# Sheet_1_copy.net
KiCad netlist of a schematic drawn in Altium Designer
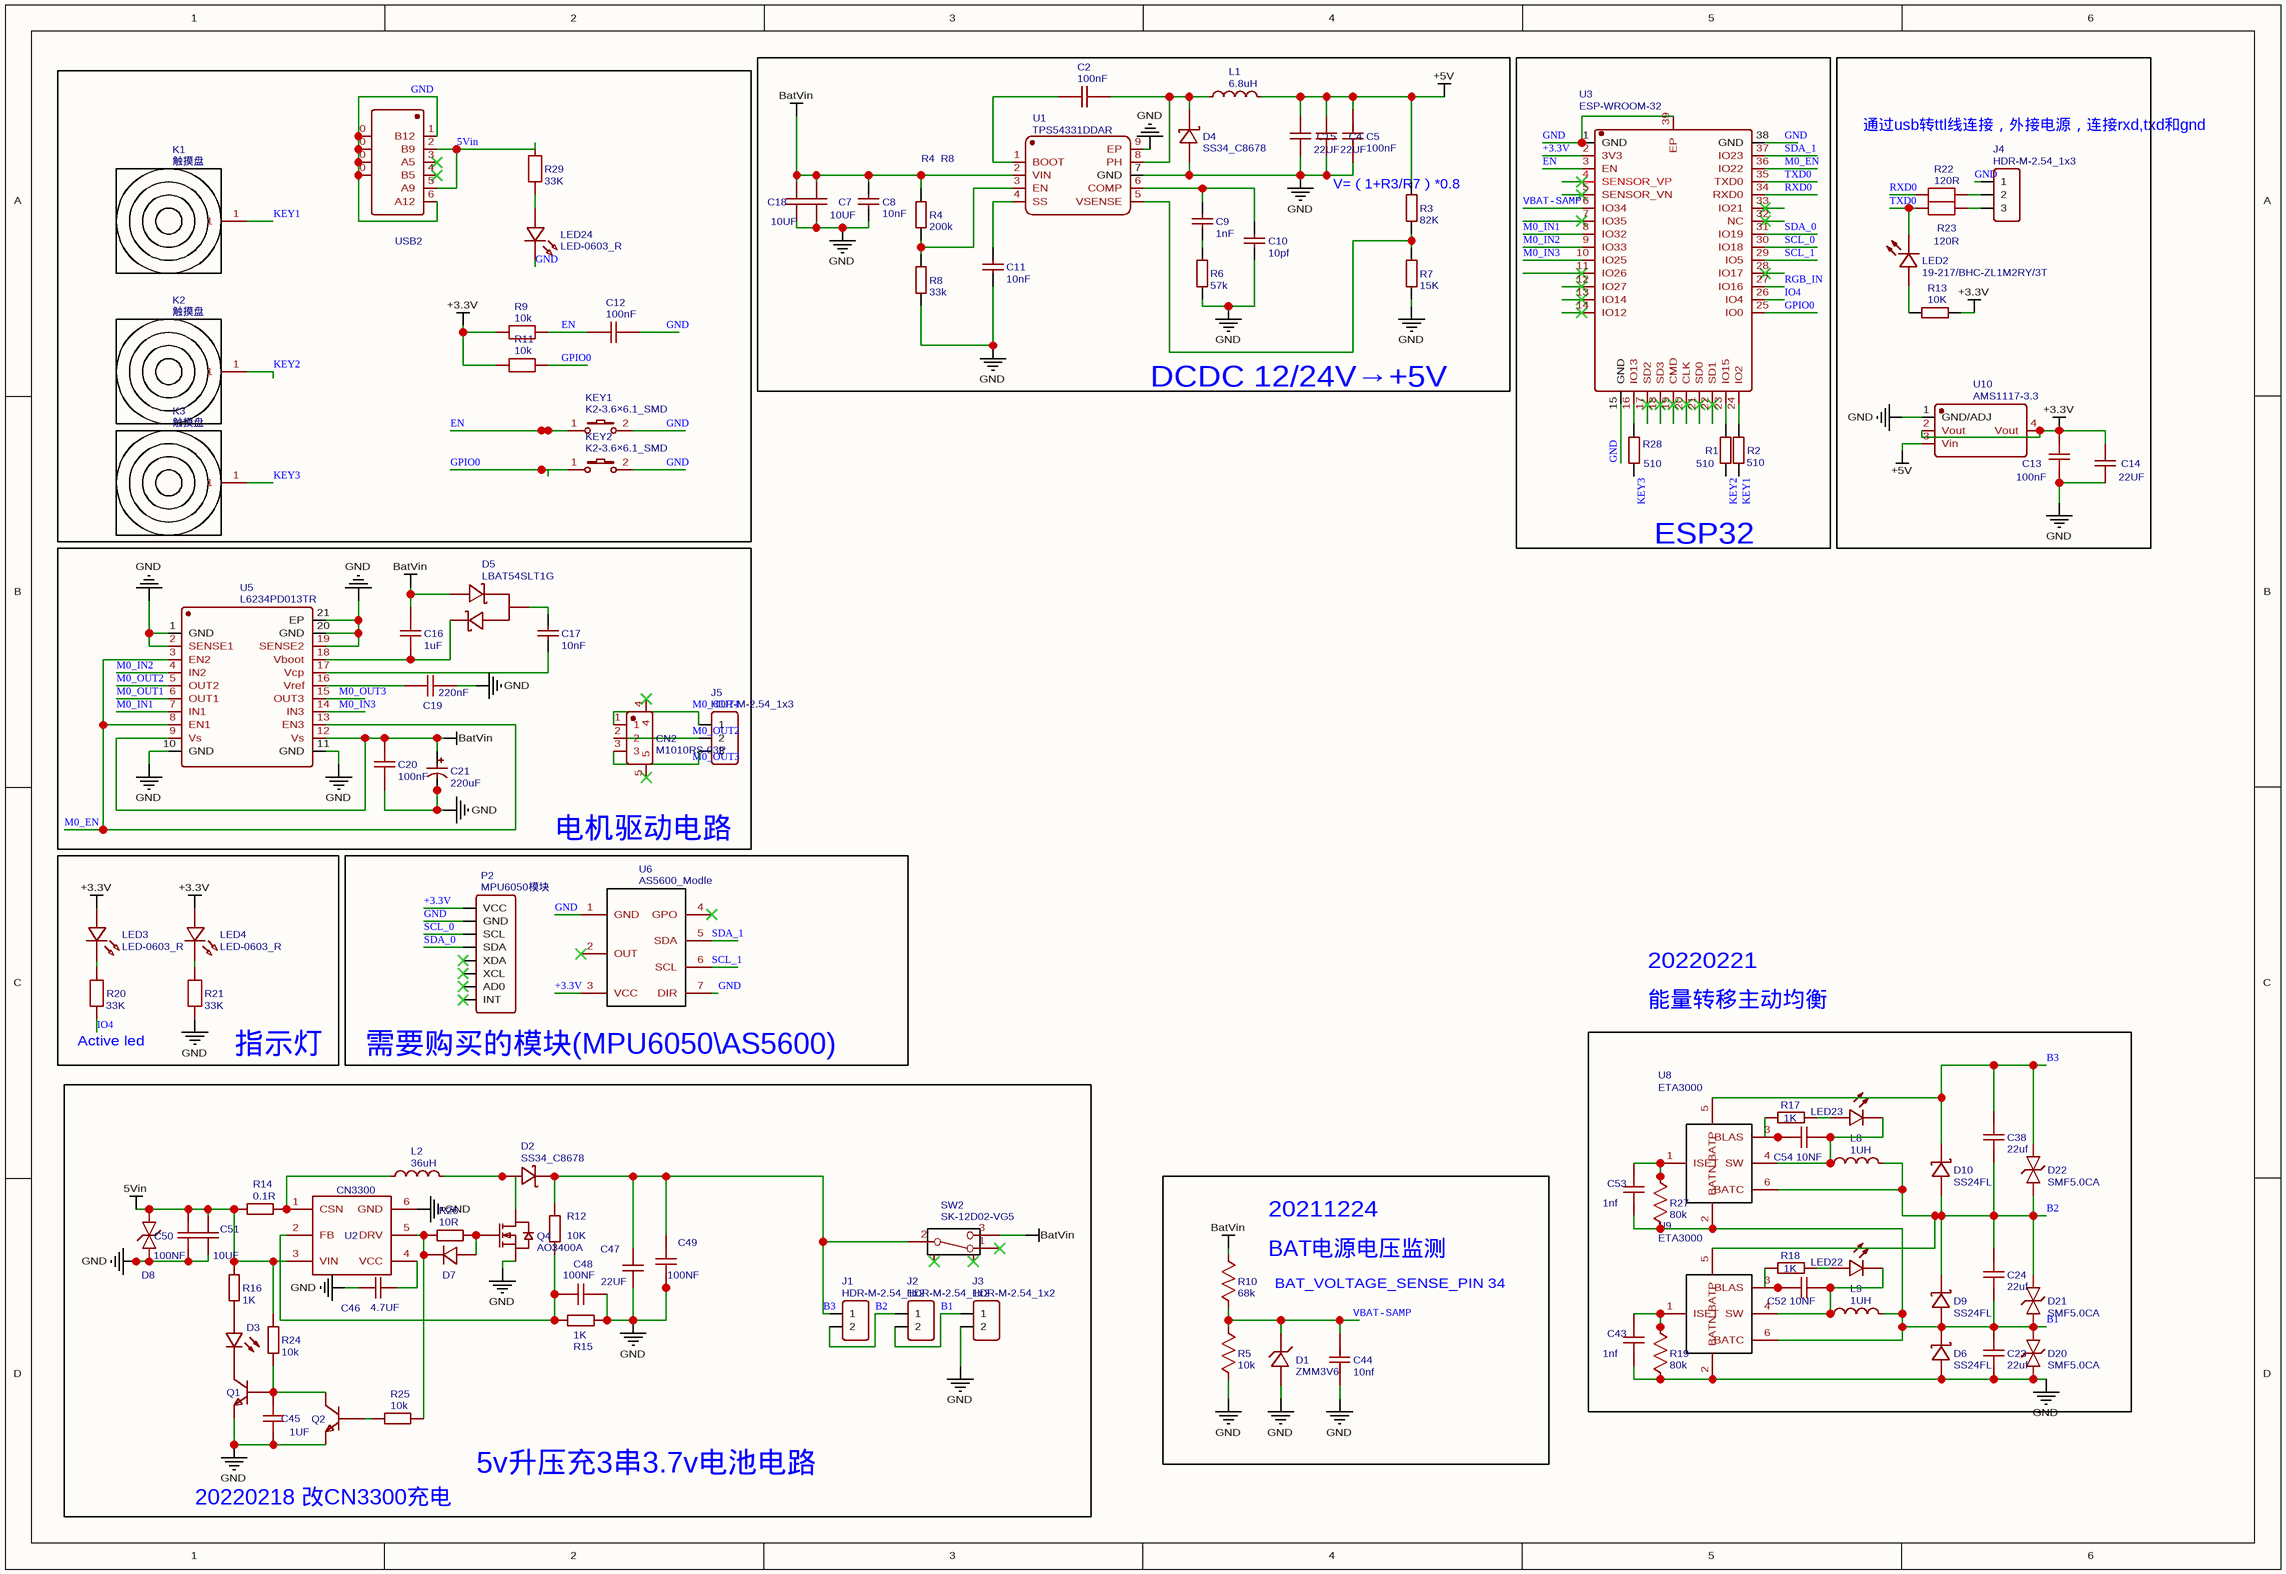
[diagram p0: Sheet_1 copy.schdoc]

(export (version "E")
  (design (tool "Eeschema 10.0.6"))
  (components
    (comp (ref "C2")
      (value "100nF")
      (fields (field (name "BOM_SUPPLIER PART") "C14663") (field (name "CONTRIBUTOR") "LCEDA_Lib"))
      (libsource (lib "altium-import") (part "root_0_100nF_"))
    )
    (comp (ref "C4")
      (value "22UF")
      (fields
        (field (name "BOM_MANUFACTURER PART") "CL31A226KPHNNNE")
        (field (name "BOM_SUPPLIER PART") "C5672")
      )
      (libsource (lib "altium-import") (part "root_1_22UF_"))
    )
    (comp (ref "C5")
      (value "100nF")
      (fields (field (name "BOM_SUPPLIER PART") "C14663") (field (name "CONTRIBUTOR") "LCEDA_Lib"))
      (libsource (lib "altium-import") (part "root_1_100nF_"))
    )
    (comp (ref "C7")
      (value "10UF")
      (fields
        (field (name "BOM_MANUFACTURER PART") "CL31A226KPHNNNE")
        (field (name "BOM_SUPPLIER PART") "C5672")
      )
      (libsource (lib "altium-import") (part "root_1_10UF_"))
    )
    (comp (ref "C8")
      (value "10nF")
      (fields
        (field (name "BOM_MANUFACTURER PART") "CC0603KRX7R9BB103")
        (field (name "BOM_SUPPLIER PART") "C100042")
      )
      (libsource (lib "altium-import") (part "root_1_10nF_"))
    )
    (comp (ref "C9")
      (value "1nF")
      (fields
        (field (name "BOM_MANUFACTURER PART") "CC0603KRX7R9BB102")
        (field (name "BOM_SUPPLIER PART") "C100040")
      )
      (libsource (lib "altium-import") (part "root_1_1nF_"))
    )
    (comp (ref "C10")
      (value "10pf")
      (fields
        (field (name "BOM_MANUFACTURER PART") "CC0603JRNPO9BN470")
        (field (name "BOM_SUPPLIER PART") "C105622")
      )
      (libsource (lib "altium-import") (part "root_1_10pf_"))
    )
    (comp (ref "C11")
      (value "10nF")
      (fields
        (field (name "BOM_MANUFACTURER PART") "CC0603KRX7R9BB103")
        (field (name "BOM_SUPPLIER PART") "C100042")
      )
      (libsource (lib "altium-import") (part "root_1_10nF_"))
    )
    (comp (ref "C12")
      (value "100nF")
      (fields (field (name "BOM_SUPPLIER PART") "C14663") (field (name "CONTRIBUTOR") "LCEDA_Lib"))
      (libsource (lib "altium-import") (part "root_0_100nF_"))
    )
    (comp (ref "C13")
      (value "100nF")
      (fields (field (name "BOM_SUPPLIER PART") "C14663") (field (name "CONTRIBUTOR") "LCEDA_Lib"))
      (libsource (lib "altium-import") (part "root_1_100nF_"))
    )
    (comp (ref "C14")
      (value "22UF")
      (fields
        (field (name "BOM_MANUFACTURER PART") "CL31A226KPHNNNE")
        (field (name "BOM_SUPPLIER PART") "C5672")
      )
      (libsource (lib "altium-import") (part "root_1_22UF_"))
    )
    (comp (ref "C15")
      (value "22UF")
      (fields
        (field (name "BOM_MANUFACTURER PART") "CL31A226KPHNNNE")
        (field (name "BOM_SUPPLIER PART") "C5672")
      )
      (libsource (lib "altium-import") (part "root_1_22UF_"))
    )
    (comp (ref "C16")
      (value "1uF")
      (fields (field (name "CONTRIBUTOR") "LCEDA_Lib"))
      (libsource (lib "altium-import") (part "root_1_1uF_"))
    )
    (comp (ref "C17")
      (value "10nF")
      (fields
        (field (name "BOM_MANUFACTURER PART") "CC0603KRX7R9BB103")
        (field (name "BOM_SUPPLIER PART") "C100042")
      )
      (libsource (lib "altium-import") (part "root_1_10nF_"))
    )
    (comp (ref "C18")
      (value "10UF")
      (fields
        (field (name "BOM_MANUFACTURER PART") "CL31A226KPHNNNE")
        (field (name "BOM_SUPPLIER PART") "C5672")
      )
      (libsource (lib "altium-import") (part "root_1_10UF_"))
    )
    (comp (ref "C19")
      (value "220nF")
      (fields (field (name "CONTRIBUTOR") "LCEDA_Lib"))
      (libsource (lib "altium-import") (part "root_0_220nF_"))
    )
    (comp (ref "C20")
      (value "100nF")
      (fields (field (name "CONTRIBUTOR") "LCEDA_Lib"))
      (libsource (lib "altium-import") (part "root_3_100nF_"))
    )
    (comp (ref "C21")
      (value "220uF")
      (fields (field (name "BOM_MANUFACTURER PART") "220uf/35V") (field (name "BOM_SUPPLIER PART") "C2063"))
      (libsource (lib "altium-import") (part "root_3_220uF_"))
    )
    (comp (ref "C23")
      (value "22uf")
      (fields (field (name "CONTRIBUTOR") "LCEDA_Lib"))
      (libsource (lib "altium-import") (part "root_1_22uf_"))
    )
    (comp (ref "C24")
      (value "22uf")
      (fields (field (name "CONTRIBUTOR") "LCEDA_Lib"))
      (libsource (lib "altium-import") (part "root_1_22uf_"))
    )
    (comp (ref "C38")
      (value "22uf")
      (fields (field (name "CONTRIBUTOR") "LCEDA_Lib"))
      (libsource (lib "altium-import") (part "root_1_22uf_"))
    )
    (comp (ref "C43")
      (value "1nf")
      (fields (field (name "CONTRIBUTOR") "LCEDA_Lib"))
      (libsource (lib "altium-import") (part "root_3_1nf_"))
    )
    (comp (ref "C44")
      (value "10nf")
      (fields (field (name "CONTRIBUTOR") "LCEDA_Lib"))
      (libsource (lib "altium-import") (part "root_1_10nf_"))
    )
    (comp (ref "C45") (value "1UF") (libsource (lib "altium-import") (part "root_0_1UF_")))
    (comp (ref "C46")
      (value "4.7UF")
      (fields
        (field (name "BOM_MANUFACTURER PART") "CL31A226KPHNNNE")
        (field (name "BOM_SUPPLIER PART") "C5672")
      )
      (libsource (lib "altium-import") (part "root_0_4.7UF_"))
    )
    (comp (ref "C47")
      (value "22UF")
      (fields
        (field (name "BOM_MANUFACTURER PART") "CL31A226KPHNNNE")
        (field (name "BOM_SUPPLIER PART") "C5672")
      )
      (libsource (lib "altium-import") (part "root_1_22UF_"))
    )
    (comp (ref "C48") (value "100NF") (libsource (lib "altium-import") (part "root_1_100NF_")))
    (comp (ref "C49") (value "100NF") (libsource (lib "") (part "root_0_100NF__1")))
    (comp (ref "C50") (value "100NF") (libsource (lib "altium-import") (part "root_0_100NF_")))
    (comp (ref "C51")
      (value "10UF")
      (fields
        (field (name "BOM_MANUFACTURER PART") "CL31A226KPHNNNE")
        (field (name "BOM_SUPPLIER PART") "C5672")
      )
      (libsource (lib "altium-import") (part "root_3_10UF_"))
    )
    (comp (ref "C52")
      (value "10NF")
      (fields (field (name "CONTRIBUTOR") "LCEDA_Lib"))
      (libsource (lib "altium-import") (part "root_0_10NF_"))
    )
    (comp (ref "C53")
      (value "1nf")
      (fields (field (name "CONTRIBUTOR") "LCEDA_Lib"))
      (libsource (lib "altium-import") (part "root_3_1nf_"))
    )
    (comp (ref "C54")
      (value "10NF")
      (fields (field (name "CONTRIBUTOR") "LCEDA_Lib"))
      (libsource (lib "altium-import") (part "root_0_10NF_"))
    )
    (comp (ref "CN2")
      (value "M1010RS-03P")
      (fields (field (name "BOM_SUPPLIER PART") "C541845") (field (name "CONTRIBUTOR") "LCSC"))
      (libsource (lib "altium-import") (part "root_0_M1010RS-03P_"))
    )
    (comp (ref "D1")
      (value "ZMM3V6")
      (fields (field (name "BOM_SUPPLIER PART") "C8057"))
      (libsource (lib "altium-import") (part "root_3_ZMM3V6_"))
    )
    (comp (ref "D2")
      (value "SS34_C8678")
      (fields (field (name "BOM_MANUFACTURER PART") "SS34") (field (name "BOM_SUPPLIER PART") "C8678"))
      (libsource (lib "altium-import") (part "root_2_SS34_C8678_"))
    )
    (comp (ref "D3")
      (value "FC-DA1608HRK-620D")
      (fields (field (name "BOM_SUPPLIER PART") "C84263"))
      (libsource (lib "altium-import") (part "root_3_FC-DA1608HRK-620D_"))
    )
    (comp (ref "D4")
      (value "SS34_C8678")
      (fields (field (name "BOM_MANUFACTURER PART") "SS34") (field (name "BOM_SUPPLIER PART") "C8678"))
      (libsource (lib "altium-import") (part "root_3_SS34_C8678_"))
    )
    (comp (ref "D5")
      (value "LBAT54SLT1G")
      (fields (field (name "BOM_SUPPLIER PART") "C12765"))
      (libsource (lib "altium-import") (part "root_0_LBAT54SLT1G_"))
    )
    (comp (ref "D6")
      (value "SS24FL")
      (fields (field (name "BOM_SUPPLIER PART") "C489144") (field (name "CONTRIBUTOR") "LCSC"))
      (libsource (lib "altium-import") (part "root_3_SS24FL_"))
    )
    (comp (ref "D7")
      (value "1N4148WS-C108805")
      (fields (field (name "BOM_MANUFACTURER PART") "1N4148WS") (field (name "BOM_SUPPLIER PART") "C108805"))
      (libsource (lib "altium-import") (part "root_0_1N4148WS-C108805_"))
    )
    (comp (ref "D8")
      (value "SJD12C6.5L01")
      (fields (field (name "BOM_SUPPLIER PART") "C313294") (field (name "CONTRIBUTOR") "LCSC"))
      (libsource (lib "altium-import") (part "root_1_SJD12C6.5L01_"))
    )
    (comp (ref "D9")
      (value "SS24FL")
      (fields (field (name "BOM_SUPPLIER PART") "C489144") (field (name "CONTRIBUTOR") "LCSC"))
      (libsource (lib "altium-import") (part "root_3_SS24FL_"))
    )
    (comp (ref "D10")
      (value "SS24FL")
      (fields (field (name "BOM_SUPPLIER PART") "C489144") (field (name "CONTRIBUTOR") "LCSC"))
      (libsource (lib "altium-import") (part "root_3_SS24FL_"))
    )
    (comp (ref "D20")
      (value "SMF5.0CA")
      (fields (field (name "BOM_SUPPLIER PART") "C908370") (field (name "CONTRIBUTOR") "LCSC"))
      (libsource (lib "altium-import") (part "root_3_SMF5.0CA_"))
    )
    (comp (ref "D21")
      (value "SMF5.0CA")
      (fields (field (name "BOM_SUPPLIER PART") "C908370") (field (name "CONTRIBUTOR") "LCSC"))
      (libsource (lib "altium-import") (part "root_3_SMF5.0CA_"))
    )
    (comp (ref "D22")
      (value "SMF5.0CA")
      (fields (field (name "BOM_SUPPLIER PART") "C908370") (field (name "CONTRIBUTOR") "LCSC"))
      (libsource (lib "altium-import") (part "root_3_SMF5.0CA_"))
    )
    (comp (ref "J1")
      (value "HDR-M-2.54_1x2")
      (fields (field (name "BOM_SUPPLIER PART") "C124375") (field (name "CONTRIBUTOR") "LCEDA_Lib"))
      (libsource (lib "altium-import") (part "root_0_HDR-M-2.54_1x2_"))
    )
    (comp (ref "J2")
      (value "HDR-M-2.54_1x2")
      (fields (field (name "BOM_SUPPLIER PART") "C124375") (field (name "CONTRIBUTOR") "LCEDA_Lib"))
      (libsource (lib "altium-import") (part "root_0_HDR-M-2.54_1x2_"))
    )
    (comp (ref "J3")
      (value "HDR-M-2.54_1x2")
      (fields (field (name "BOM_SUPPLIER PART") "C124375") (field (name "CONTRIBUTOR") "LCEDA_Lib"))
      (libsource (lib "altium-import") (part "root_0_HDR-M-2.54_1x2_"))
    )
    (comp (ref "J4")
      (value "HDR-M-2.54_1x3")
      (fields (field (name "BOM_SUPPLIER PART") "C180248") (field (name "CONTRIBUTOR") "LCEDA_Lib"))
      (libsource (lib "altium-import") (part "root_0_HDR-M-2.54_1x3_"))
    )
    (comp (ref "J5")
      (value "HDR-M-2.54_1x3")
      (fields (field (name "BOM_SUPPLIER PART") "C180248") (field (name "CONTRIBUTOR") "LCEDA_Lib"))
      (libsource (lib "altium-import") (part "root_0_HDR-M-2.54_1x3_"))
    )
    (comp (ref "K1")
      (value "触摸盘")
      (fields (field (name "CONTRIBUTOR") "Lisdon"))
      (libsource (lib "altium-import") (part "root_0_触摸盘_"))
    )
    (comp (ref "K2")
      (value "触摸盘")
      (fields (field (name "CONTRIBUTOR") "Lisdon"))
      (libsource (lib "altium-import") (part "root_0_触摸盘_"))
    )
    (comp (ref "K3")
      (value "触摸盘")
      (fields (field (name "CONTRIBUTOR") "Lisdon"))
      (libsource (lib "altium-import") (part "root_0_触摸盘_"))
    )
    (comp (ref "KEY1")
      (value "K2-3.6×6.1_SMD")
      (fields
        (field (name "BOM_SUPPLIER PART") "C118141")
        (field (name "BOM_MANUFACTURER PART") "K2-1107ST-A4SW-06")
        (field (name "CONTRIBUTOR") "LCEDA_Lib")
      )
      (libsource (lib "altium-import") (part "root_0_K2-3.6×6.1_SMD_"))
    )
    (comp (ref "KEY2")
      (value "K2-3.6×6.1_SMD")
      (fields
        (field (name "BOM_SUPPLIER PART") "C118141")
        (field (name "BOM_MANUFACTURER PART") "K2-1107ST-A4SW-06")
        (field (name "CONTRIBUTOR") "LCEDA_Lib")
      )
      (libsource (lib "altium-import") (part "root_0_K2-3.6×6.1_SMD_"))
    )
    (comp (ref "L1")
      (value "6.8uH")
      (fields
        (field (name "BOM_SUPPLIER PART") "C357230")
        (field (name "BOM_MANUFACTURER PART") "TMPC0624H-6R8MG-D")
        (field (name "CONTRIBUTOR") "LCSC")
      )
      (libsource (lib "altium-import") (part "root_0_6.8uH_"))
    )
    (comp (ref "L2")
      (value "36uH")
      (fields
        (field (name "BOM_SUPPLIER PART") "C357230")
        (field (name "BOM_MANUFACTURER PART") "TMPC0624H-6R8MG-D")
        (field (name "CONTRIBUTOR") "LCSC")
      )
      (libsource (lib "altium-import") (part "root_0_36uH_"))
    )
    (comp (ref "L8")
      (value "1UH")
      (fields
        (field (name "BOM_SUPPLIER PART") "C241390")
        (field (name "BOM_MANUFACTURER PART") "YXMAA0603-1R5M-ANF")
        (field (name "CONTRIBUTOR") "LCEDA_Lib")
      )
      (libsource (lib "altium-import") (part "root_0_1UH_"))
    )
    (comp (ref "L9")
      (value "1UH")
      (fields
        (field (name "BOM_SUPPLIER PART") "C241390")
        (field (name "BOM_MANUFACTURER PART") "YXMAA0603-1R5M-ANF")
        (field (name "CONTRIBUTOR") "LCEDA_Lib")
      )
      (libsource (lib "altium-import") (part "root_0_1UH_"))
    )
    (comp (ref "LED2")
      (value "19-217/BHC-ZL1M2RY/3T")
      (fields (field (name "BOM_SUPPLIER PART") "C72041"))
      (libsource (lib "altium-import") (part "root_3_19-217/BHC-ZL1M2RY/3T_"))
    )
    (comp (ref "LED3")
      (value "LED-0603_R")
      (fields
        (field (name "BOM_MANUFACTURER PART") "19-217/R6C-AL1M2VY/3T")
        (field (name "BOM_SUPPLIER PART") "C72044")
        (field (name "CONTRIBUTOR") "LCEDA_01")
      )
      (libsource (lib "altium-import") (part "root_3_LED-0603_R_"))
    )
    (comp (ref "LED4")
      (value "LED-0603_R")
      (fields
        (field (name "BOM_MANUFACTURER PART") "19-217/R6C-AL1M2VY/3T")
        (field (name "BOM_SUPPLIER PART") "C72044")
        (field (name "CONTRIBUTOR") "LCEDA_01")
      )
      (libsource (lib "altium-import") (part "root_3_LED-0603_R_"))
    )
    (comp (ref "LED22")
      (value "FC-DA1608HRK-620D")
      (fields (field (name "BOM_SUPPLIER PART") "C84263"))
      (libsource (lib "altium-import") (part "root_0_FC-DA1608HRK-620D_"))
    )
    (comp (ref "LED23")
      (value "FC-DA1608HRK-620D")
      (fields (field (name "BOM_SUPPLIER PART") "C84263"))
      (libsource (lib "altium-import") (part "root_0_FC-DA1608HRK-620D_"))
    )
    (comp (ref "LED24")
      (value "LED-0603_R")
      (fields
        (field (name "BOM_MANUFACTURER PART") "19-217/R6C-AL1M2VY/3T")
        (field (name "BOM_SUPPLIER PART") "C72044")
        (field (name "CONTRIBUTOR") "LCEDA_01")
      )
      (libsource (lib "altium-import") (part "root_3_LED-0603_R_"))
    )
    (comp (ref "P2") (value "MPU6050模块") (libsource (lib "altium-import") (part "root_0_MPU6050模块_")))
    (comp (ref "Q1")
      (value "SS8050_C177739")
      (fields
        (field (name "BOM_SUPPLIER PART") "C177739")
        (field (name "BOM_MANUFACTURER PART") "SS8050")
        (field (name "CONTRIBUTOR") "LCSC")
      )
      (libsource (lib "altium-import") (part "root_0_SS8050_C177739_"))
    )
    (comp (ref "Q2")
      (value "SS8050_C177739")
      (fields
        (field (name "BOM_SUPPLIER PART") "C177739")
        (field (name "BOM_MANUFACTURER PART") "SS8050")
        (field (name "CONTRIBUTOR") "LCSC")
      )
      (libsource (lib "altium-import") (part "root_0_SS8050_C177739_"))
    )
    (comp (ref "Q4")
      (value "AO3400A")
      (fields (field (name "BOM_SUPPLIER PART") "C20917"))
      (libsource (lib "altium-import") (part "root_0_AO3400A_"))
    )
    (comp (ref "R1")
      (value "510")
      (fields
        (field (name "BOM_MANUFACTURER PART") "0603WAF1002T5E")
        (field (name "BOM_SUPPLIER PART") "C25804")
      )
      (libsource (lib "altium-import") (part "root_1_510_"))
    )
    (comp (ref "R2")
      (value "510")
      (fields
        (field (name "BOM_MANUFACTURER PART") "0603WAF1002T5E")
        (field (name "BOM_SUPPLIER PART") "C25804")
      )
      (libsource (lib "altium-import") (part "root_1_510_"))
    )
    (comp (ref "R3")
      (value "82K")
      (fields
        (field (name "BOM_MANUFACTURER PART") "0603WAF1022T5E")
        (field (name "BOM_SUPPLIER PART") "C22772")
      )
      (libsource (lib "altium-import") (part "root_1_82K_"))
    )
    (comp (ref "R4")
      (value "200k")
      (fields
        (field (name "BOM_MANUFACTURER PART") "0603WAF3323T5E")
        (field (name "BOM_SUPPLIER PART") "C23139")
      )
      (libsource (lib "altium-import") (part "root_1_200k_"))
    )
    (comp (ref "R5") (value "10k") (libsource (lib "altium-import") (part "root_1_10k_")))
    (comp (ref "R6")
      (value "57k")
      (fields
        (field (name "BOM_MANUFACTURER PART") "0603WAF2492T5E")
        (field (name "BOM_SUPPLIER PART") "C25962")
      )
      (libsource (lib "altium-import") (part "root_1_57k_"))
    )
    (comp (ref "R7")
      (value "15K")
      (fields
        (field (name "BOM_MANUFACTURER PART") "0603WAF3241T5E")
        (field (name "BOM_SUPPLIER PART") "C22994")
      )
      (libsource (lib "altium-import") (part "root_1_15K_"))
    )
    (comp (ref "R8")
      (value "33k")
      (fields
        (field (name "BOM_MANUFACTURER PART") "0603WAF6812T5E")
        (field (name "BOM_SUPPLIER PART") "C25976")
      )
      (libsource (lib "altium-import") (part "root_1_33k_"))
    )
    (comp (ref "R9")
      (value "10k")
      (fields (field (name "CONTRIBUTOR") "LCEDA_Lib"))
      (libsource (lib "altium-import") (part "root_0_10k_"))
    )
    (comp (ref "R10") (value "68k") (libsource (lib "altium-import") (part "root_1_68k_")))
    (comp (ref "R11")
      (value "10k")
      (fields (field (name "CONTRIBUTOR") "LCEDA_Lib"))
      (libsource (lib "altium-import") (part "root_0_10k_"))
    )
    (comp (ref "R12")
      (value "10K")
      (fields
        (field (name "BOM_MANUFACTURER PART") "TC0525D1001T5E")
        (field (name "BOM_SUPPLIER PART") "C44535")
      )
      (libsource (lib "altium-import") (part "root_1_10K_"))
    )
    (comp (ref "R13")
      (value "10K")
      (fields
        (field (name "BOM_MANUFACTURER PART") "0603WAF1002T5E")
        (field (name "BOM_SUPPLIER PART") "C25804")
      )
      (libsource (lib "altium-import") (part "root_0_10K_"))
    )
    (comp (ref "R14")
      (value "0.1R")
      (fields
        (field (name "BOM_MANUFACTURER PART") "RS-03K103JT")
        (field (name "BOM_SUPPLIER PART") "C73809")
      )
      (libsource (lib "altium-import") (part "root_0_0.1R_"))
    )
    (comp (ref "R15")
      (value "1K")
      (fields
        (field (name "BOM_MANUFACTURER PART") "TC0525D1001T5E")
        (field (name "BOM_SUPPLIER PART") "C44535")
      )
      (libsource (lib "altium-import") (part "root_0_1K_"))
    )
    (comp (ref "R16")
      (value "1K")
      (fields
        (field (name "BOM_MANUFACTURER PART") "RS-03K103JT")
        (field (name "BOM_SUPPLIER PART") "C73809")
      )
      (libsource (lib "altium-import") (part "root_1_1K_"))
    )
    (comp (ref "R17")
      (value "1K")
      (fields
        (field (name "BOM_MANUFACTURER PART") "RS-03K103JT")
        (field (name "BOM_SUPPLIER PART") "C73809")
      )
      (libsource (lib "altium-import") (part "root_2_1K_"))
    )
    (comp (ref "R18")
      (value "1K")
      (fields
        (field (name "BOM_MANUFACTURER PART") "RS-03K103JT")
        (field (name "BOM_SUPPLIER PART") "C73809")
      )
      (libsource (lib "altium-import") (part "root_2_1K_"))
    )
    (comp (ref "R19")
      (value "80k")
      (fields (field (name "CONTRIBUTOR") "LCEDA_Lib"))
      (libsource (lib "altium-import") (part "root_1_80k_"))
    )
    (comp (ref "R20")
      (value "33K")
      (fields (field (name "CONTRIBUTOR") "LCEDA_Lib"))
      (libsource (lib "altium-import") (part "root_1_33K_"))
    )
    (comp (ref "R21")
      (value "33K")
      (fields (field (name "CONTRIBUTOR") "LCEDA_Lib"))
      (libsource (lib "altium-import") (part "root_1_33K_"))
    )
    (comp (ref "R22")
      (value "120R")
      (fields (field (name "BOM_SUPPLIER PART") "C103256") (field (name "CONTRIBUTOR") "LCEDA_Lib"))
      (libsource (lib "altium-import") (part "root_0_120R_"))
    )
    (comp (ref "R23")
      (value "120R")
      (fields (field (name "BOM_SUPPLIER PART") "C103256") (field (name "CONTRIBUTOR") "LCEDA_Lib"))
      (libsource (lib "altium-import") (part "root_0_120R_"))
    )
    (comp (ref "R24")
      (value "10k")
      (fields
        (field (name "BOM_MANUFACTURER PART") "RS-03K103JT")
        (field (name "BOM_SUPPLIER PART") "C73809")
      )
      (libsource (lib "") (part "root_1_10k__1"))
    )
    (comp (ref "R25")
      (value "10k")
      (fields
        (field (name "BOM_MANUFACTURER PART") "RS-03K103JT")
        (field (name "BOM_SUPPLIER PART") "C73809")
      )
      (libsource (lib "altium-import") (part "root_2_10k_"))
    )
    (comp (ref "R26")
      (value "10R")
      (fields
        (field (name "BOM_MANUFACTURER PART") "RS-03K103JT")
        (field (name "BOM_SUPPLIER PART") "C73809")
      )
      (libsource (lib "altium-import") (part "root_2_10R_"))
    )
    (comp (ref "R27")
      (value "80k")
      (fields (field (name "CONTRIBUTOR") "LCEDA_Lib"))
      (libsource (lib "altium-import") (part "root_1_80k_"))
    )
    (comp (ref "R28")
      (value "510")
      (fields
        (field (name "BOM_MANUFACTURER PART") "0603WAF1002T5E")
        (field (name "BOM_SUPPLIER PART") "C25804")
      )
      (libsource (lib "altium-import") (part "root_1_510_"))
    )
    (comp (ref "R29")
      (value "33K")
      (fields (field (name "CONTRIBUTOR") "LCEDA_Lib"))
      (libsource (lib "altium-import") (part "root_1_33K_"))
    )
    (comp (ref "SW2")
      (value "SK-12D02-VG5")
      (fields (field (name "BOM_SUPPLIER PART") "C136722") (field (name "CONTRIBUTOR") "LCSC"))
      (libsource (lib "altium-import") (part "root_0_SK-12D02-VG5_"))
    )
    (comp (ref "U1")
      (value "TPS54331DDAR")
      (fields (field (name "BOM_SUPPLIER PART") "C90761") (field (name "CONTRIBUTOR") "13471635540"))
      (libsource (lib "altium-import") (part "root_0_TPS54331DDAR_"))
    )
    (comp (ref "U2")
      (value "CN3300")
      (fields (field (name "BOM_SUPPLIER PART") "C52375"))
      (libsource (lib "altium-import") (part "root_0_CN3300_"))
    )
    (comp (ref "U3")
      (value "ESP-WROOM-32")
      (fields (field (name "BOM_SUPPLIER PART") "C95209"))
      (libsource (lib "altium-import") (part "root_0_ESP-WROOM-32_"))
    )
    (comp (ref "U5")
      (value "L6234PD013TR")
      (fields (field (name "BOM_SUPPLIER PART") "C77581"))
      (libsource (lib "altium-import") (part "root_0_L6234PD013TR_"))
    )
    (comp (ref "U6")
      (value "AS5600_Modle")
      (fields (field (name "CONTRIBUTOR") "45coll"))
      (libsource (lib "altium-import") (part "root_0_AS5600_Modle_"))
    )
    (comp (ref "U8")
      (value "ETA3000")
      (fields (field (name "CONTRIBUTOR") "mozixi"))
      (libsource (lib "altium-import") (part "root_0_ETA3000_"))
    )
    (comp (ref "U9")
      (value "ETA3000")
      (fields (field (name "CONTRIBUTOR") "mozixi"))
      (libsource (lib "altium-import") (part "root_0_ETA3000_"))
    )
    (comp (ref "U10")
      (value "AMS1117-3.3")
      (fields (field (name "BOM_SUPPLIER PART") "C6186"))
      (libsource (lib "altium-import") (part "root_0_AMS1117-3.3_"))
    )
    (comp (ref "USB2")
      (value "TYPE-C-31-M-17")
      (fields (field (name "BOM_SUPPLIER PART") "C283540") (field (name "CONTRIBUTOR") "LCSC"))
      (libsource (lib "altium-import") (part "root_0_TYPE-C-31-M-17_"))
    )
  )
  (nets
    (net (code "1") (name "+3.3V") (class "Default")
      (node (ref "C13") (pin "2") (pinfunction "2_2") (pintype "passive"))
      (node (ref "C14") (pin "2") (pinfunction "2_2") (pintype "passive"))
      (node (ref "LED3") (pin "1") (pinfunction "1_1") (pintype "passive"))
      (node (ref "LED4") (pin "1") (pinfunction "1_1") (pintype "passive"))
      (node (ref "P2") (pin "1") (pinfunction "VCC_1") (pintype "passive"))
      (node (ref "R11") (pin "1") (pinfunction "1_1") (pintype "passive"))
      (node (ref "R13") (pin "2") (pinfunction "2_2") (pintype "passive"))
      (node (ref "R9") (pin "1") (pinfunction "1_1") (pintype "passive"))
      (node (ref "U10") (pin "2") (pinfunction "Vout_2") (pintype "passive"))
      (node (ref "U10") (pin "4") (pinfunction "Vout_4") (pintype "passive"))
      (node (ref "U3") (pin "2") (pinfunction "3V3_2") (pintype "passive"))
      (node (ref "U6") (pin "3") (pinfunction "VCC_3") (pintype "passive"))
    )
    (net (code "2") (name "+5V") (class "Default")
      (node (ref "C15") (pin "2") (pinfunction "2_2") (pintype "passive"))
      (node (ref "C4") (pin "2") (pinfunction "2_2") (pintype "passive"))
      (node (ref "C5") (pin "2") (pinfunction "2_2") (pintype "passive"))
      (node (ref "L1") (pin "2") (pinfunction "2_2") (pintype "passive"))
      (node (ref "R3") (pin "2") (pinfunction "2_2") (pintype "passive"))
      (node (ref "U10") (pin "3") (pinfunction "Vin_3") (pintype "passive"))
    )
    (net (code "3") (name "/B1") (class "Default")
      (node (ref "C23") (pin "2") (pinfunction "2_2") (pintype "passive"))
      (node (ref "C24") (pin "1") (pinfunction "1_1") (pintype "passive"))
      (node (ref "C53") (pin "2") (pinfunction "2_2") (pintype "passive"))
      (node (ref "D20") (pin "1") (pinfunction "1_1") (pintype "passive"))
      (node (ref "D21") (pin "2") (pinfunction "2_2") (pintype "passive"))
      (node (ref "D6") (pin "1") (pinfunction "K_1") (pintype "passive"))
      (node (ref "D9") (pin "2") (pinfunction "A_2") (pintype "passive"))
      (node (ref "J2") (pin "2") (pinfunction "2_2") (pintype "passive"))
      (node (ref "J3") (pin "1") (pinfunction "1_1") (pintype "passive"))
      (node (ref "L9") (pin "2") (pinfunction "2_2") (pintype "passive"))
      (node (ref "R27") (pin "1") (pinfunction "1_1") (pintype "passive"))
      (node (ref "U8") (pin "2") (pinfunction "BATN_2") (pintype "passive"))
      (node (ref "U9") (pin "6") (pinfunction "BATC_6") (pintype "passive"))
    )
    (net (code "4") (name "/B2") (class "Default")
      (node (ref "C24") (pin "2") (pinfunction "2_2") (pintype "passive"))
      (node (ref "C38") (pin "1") (pinfunction "1_1") (pintype "passive"))
      (node (ref "D10") (pin "2") (pinfunction "A_2") (pintype "passive"))
      (node (ref "D21") (pin "1") (pinfunction "1_1") (pintype "passive"))
      (node (ref "D22") (pin "2") (pinfunction "2_2") (pintype "passive"))
      (node (ref "D9") (pin "1") (pinfunction "K_1") (pintype "passive"))
      (node (ref "J1") (pin "2") (pinfunction "2_2") (pintype "passive"))
      (node (ref "J2") (pin "1") (pinfunction "1_1") (pintype "passive"))
      (node (ref "L8") (pin "2") (pinfunction "2_2") (pintype "passive"))
      (node (ref "U8") (pin "6") (pinfunction "BATC_6") (pintype "passive"))
      (node (ref "U9") (pin "5") (pinfunction "BATP_5") (pintype "passive"))
    )
    (net (code "5") (name "/B3") (class "Default")
      (node (ref "C38") (pin "2") (pinfunction "2_2") (pintype "passive"))
      (node (ref "C47") (pin "2") (pinfunction "2_2") (pintype "passive"))
      (node (ref "C49") (pin "2") (pinfunction "2_2") (pintype "passive"))
      (node (ref "D10") (pin "1") (pinfunction "K_1") (pintype "passive"))
      (node (ref "D2") (pin "1") (pinfunction "K_1") (pintype "passive"))
      (node (ref "D22") (pin "1") (pinfunction "1_1") (pintype "passive"))
      (node (ref "J1") (pin "1") (pinfunction "1_1") (pintype "passive"))
      (node (ref "R12") (pin "2") (pinfunction "2_2") (pintype "passive"))
      (node (ref "SW2") (pin "2") (pinfunction "2_2") (pintype "passive"))
      (node (ref "U8") (pin "5") (pinfunction "BATP_5") (pintype "passive"))
    )
    (net (code "6") (name "/EN") (class "Default")
      (node (ref "C12") (pin "1") (pinfunction "1_1") (pintype "passive"))
      (node (ref "KEY1") (pin "1") (pinfunction "1_1") (pintype "passive"))
      (node (ref "R9") (pin "2") (pinfunction "2_2") (pintype "passive"))
      (node (ref "U3") (pin "3") (pinfunction "EN_3") (pintype "passive"))
    )
    (net (code "7") (name "/GPIO0") (class "Default")
      (node (ref "KEY2") (pin "1") (pinfunction "1_1") (pintype "passive"))
      (node (ref "R11") (pin "2") (pinfunction "2_2") (pintype "passive"))
      (node (ref "U3") (pin "25") (pinfunction "IO0_25") (pintype "passive"))
    )
    (net (code "8") (name "/IO4") (class "Default")
      (node (ref "R20") (pin "1") (pinfunction "1_1") (pintype "passive"))
      (node (ref "U3") (pin "26") (pinfunction "IO4_26") (pintype "passive"))
    )
    (net (code "9") (name "/KEY1") (class "Default")
      (node (ref "K1") (pin "1") (pinfunction "1_1") (pintype "passive"))
      (node (ref "R2") (pin "1") (pinfunction "1_1") (pintype "passive"))
    )
    (net (code "10") (name "/KEY2") (class "Default")
      (node (ref "K2") (pin "1") (pinfunction "1_1") (pintype "passive"))
      (node (ref "R1") (pin "1") (pinfunction "1_1") (pintype "passive"))
    )
    (net (code "11") (name "/KEY3") (class "Default")
      (node (ref "K3") (pin "1") (pinfunction "1_1") (pintype "passive"))
      (node (ref "R28") (pin "1") (pinfunction "1_1") (pintype "passive"))
    )
    (net (code "12") (name "/M0_EN") (class "Default")
      (node (ref "U3") (pin "36") (pinfunction "IO22_36") (pintype "passive"))
      (node (ref "U5") (pin "13") (pinfunction "EN3_13") (pintype "passive"))
      (node (ref "U5") (pin "3") (pinfunction "EN2_3") (pintype "passive"))
      (node (ref "U5") (pin "8") (pinfunction "EN1_8") (pintype "passive"))
    )
    (net (code "13") (name "/M0_IN1") (class "Default")
      (node (ref "U3") (pin "8") (pinfunction "IO32_8") (pintype "passive"))
      (node (ref "U5") (pin "7") (pinfunction "IN1_7") (pintype "passive"))
    )
    (net (code "14") (name "/M0_IN2") (class "Default")
      (node (ref "U3") (pin "9") (pinfunction "IO33_9") (pintype "passive"))
      (node (ref "U5") (pin "4") (pinfunction "IN2_4") (pintype "passive"))
    )
    (net (code "15") (name "/M0_IN3") (class "Default")
      (node (ref "U3") (pin "10") (pinfunction "IO25_10") (pintype "passive"))
      (node (ref "U5") (pin "14") (pinfunction "IN3_14") (pintype "passive"))
    )
    (net (code "16") (name "/M0_OUT1") (class "Default")
      (node (ref "CN2") (pin "1") (pinfunction "1_1") (pintype "passive"))
      (node (ref "J5") (pin "1") (pinfunction "1_1") (pintype "passive"))
      (node (ref "U5") (pin "6") (pinfunction "OUT1_6") (pintype "passive"))
    )
    (net (code "17") (name "/M0_OUT2") (class "Default")
      (node (ref "CN2") (pin "2") (pinfunction "2_2") (pintype "passive"))
      (node (ref "J5") (pin "2") (pinfunction "2_2") (pintype "passive"))
      (node (ref "U5") (pin "5") (pinfunction "OUT2_5") (pintype "passive"))
    )
    (net (code "18") (name "/M0_OUT3") (class "Default")
      (node (ref "CN2") (pin "3") (pinfunction "3_3") (pintype "passive"))
      (node (ref "J5") (pin "3") (pinfunction "3_3") (pintype "passive"))
      (node (ref "U5") (pin "15") (pinfunction "OUT3_15") (pintype "passive"))
    )
    (net (code "19") (name "/RGB_IN") (class "Default")
      (node (ref "U3") (pin "27") (pinfunction "IO16_27") (pintype "passive"))
    )
    (net (code "20") (name "/RXD0") (class "Default")
      (node (ref "R22") (pin "1") (pinfunction "1_1") (pintype "passive"))
      (node (ref "U3") (pin "34") (pinfunction "RXD0_34") (pintype "passive"))
    )
    (net (code "21") (name "/SCL_0") (class "Default")
      (node (ref "P2") (pin "3") (pinfunction "SCL_3") (pintype "passive"))
      (node (ref "U3") (pin "30") (pinfunction "IO18_30") (pintype "passive"))
    )
    (net (code "22") (name "/SCL_1") (class "Default")
      (node (ref "U3") (pin "29") (pinfunction "IO5_29") (pintype "passive"))
      (node (ref "U6") (pin "6") (pinfunction "SCL_6") (pintype "passive"))
    )
    (net (code "23") (name "/SDA_0") (class "Default")
      (node (ref "P2") (pin "4") (pinfunction "SDA_4") (pintype "passive"))
      (node (ref "U3") (pin "31") (pinfunction "IO19_31") (pintype "passive"))
    )
    (net (code "24") (name "/SDA_1") (class "Default")
      (node (ref "U3") (pin "37") (pinfunction "IO23_37") (pintype "passive"))
      (node (ref "U6") (pin "5") (pinfunction "SDA_5") (pintype "passive"))
    )
    (net (code "25") (name "/TXD0") (class "Default")
      (node (ref "LED2") (pin "2") (pinfunction "K_2") (pintype "passive"))
      (node (ref "R23") (pin "1") (pinfunction "1_1") (pintype "passive"))
      (node (ref "U3") (pin "35") (pinfunction "TXD0_35") (pintype "passive"))
    )
    (net (code "26") (name "/VBAT-SAMP") (class "Default")
      (node (ref "C44") (pin "2") (pinfunction "2_2") (pintype "passive"))
      (node (ref "D1") (pin "1") (pinfunction "C_1") (pintype "passive"))
      (node (ref "R10") (pin "1") (pinfunction "1_1") (pintype "passive"))
      (node (ref "R5") (pin "2") (pinfunction "2_2") (pintype "passive"))
      (node (ref "U3") (pin "6") (pinfunction "IO34_6") (pintype "passive"))
    )
    (net (code "27") (name "5Vin") (class "Default")
      (node (ref "C50") (pin "2") (pinfunction "2_2") (pintype "passive"))
      (node (ref "C51") (pin "1") (pinfunction "1_1") (pintype "passive"))
      (node (ref "D8") (pin "2") (pinfunction "2_2") (pintype "passive"))
      (node (ref "R14") (pin "1") (pinfunction "1_1") (pintype "passive"))
      (node (ref "R16") (pin "2") (pinfunction "2_2") (pintype "passive"))
      (node (ref "R24") (pin "2") (pinfunction "2_2") (pintype "passive"))
      (node (ref "R29") (pin "2") (pinfunction "2_2") (pintype "passive"))
      (node (ref "U2") (pin "3") (pinfunction "VIN_3") (pintype "passive"))
      (node (ref "USB2") (pin "2") (pinfunction "B9_2") (pintype "passive"))
      (node (ref "USB2") (pin "5") (pinfunction "A9_5") (pintype "passive"))
    )
    (net (code "28") (name "BatVin") (class "Default")
      (node (ref "C16") (pin "2") (pinfunction "2_2") (pintype "passive"))
      (node (ref "C18") (pin "2") (pinfunction "2_2") (pintype "passive"))
      (node (ref "C20") (pin "1") (pinfunction "1_1") (pintype "passive"))
      (node (ref "C21") (pin "1") (pinfunction "1_1") (pintype "passive"))
      (node (ref "C7") (pin "2") (pinfunction "2_2") (pintype "passive"))
      (node (ref "C8") (pin "2") (pinfunction "2_2") (pintype "passive"))
      (node (ref "D5") (pin "1") (pinfunction "A_1") (pintype "passive"))
      (node (ref "R10") (pin "2") (pinfunction "2_2") (pintype "passive"))
      (node (ref "R4") (pin "2") (pinfunction "2_2") (pintype "passive"))
      (node (ref "SW2") (pin "3") (pinfunction "3_3") (pintype "passive"))
      (node (ref "U1") (pin "2") (pinfunction "VIN_2") (pintype "passive"))
      (node (ref "U5") (pin "12") (pinfunction "Vs_12") (pintype "passive"))
      (node (ref "U5") (pin "9") (pinfunction "Vs_9") (pintype "passive"))
    )
    (net (code "29") (name "GND") (class "Default")
      (node (ref "C10") (pin "1") (pinfunction "1_1") (pintype "passive"))
      (node (ref "C11") (pin "1") (pinfunction "1_1") (pintype "passive"))
      (node (ref "C12") (pin "2") (pinfunction "2_2") (pintype "passive"))
      (node (ref "C13") (pin "1") (pinfunction "1_1") (pintype "passive"))
      (node (ref "C14") (pin "1") (pinfunction "1_1") (pintype "passive"))
      (node (ref "C15") (pin "1") (pinfunction "1_1") (pintype "passive"))
      (node (ref "C18") (pin "1") (pinfunction "1_1") (pintype "passive"))
      (node (ref "C19") (pin "2") (pinfunction "2_2") (pintype "passive"))
      (node (ref "C20") (pin "2") (pinfunction "2_2") (pintype "passive"))
      (node (ref "C21") (pin "2") (pinfunction "2_2") (pintype "passive"))
      (node (ref "C23") (pin "1") (pinfunction "1_1") (pintype "passive"))
      (node (ref "C4") (pin "1") (pinfunction "1_1") (pintype "passive"))
      (node (ref "C43") (pin "2") (pinfunction "2_2") (pintype "passive"))
      (node (ref "C44") (pin "1") (pinfunction "1_1") (pintype "passive"))
      (node (ref "C45") (pin "1") (pinfunction "1_1") (pintype "passive"))
      (node (ref "C46") (pin "1") (pinfunction "1_1") (pintype "passive"))
      (node (ref "C47") (pin "1") (pinfunction "1_1") (pintype "passive"))
      (node (ref "C48") (pin "1") (pinfunction "1_1") (pintype "passive"))
      (node (ref "C49") (pin "1") (pinfunction "1_1") (pintype "passive"))
      (node (ref "C5") (pin "1") (pinfunction "1_1") (pintype "passive"))
      (node (ref "C50") (pin "1") (pinfunction "1_1") (pintype "passive"))
      (node (ref "C51") (pin "2") (pinfunction "2_2") (pintype "passive"))
      (node (ref "C7") (pin "1") (pinfunction "1_1") (pintype "passive"))
      (node (ref "C8") (pin "1") (pinfunction "1_1") (pintype "passive"))
      (node (ref "D1") (pin "2") (pinfunction "A_2") (pintype "passive"))
      (node (ref "D20") (pin "2") (pinfunction "2_2") (pintype "passive"))
      (node (ref "D4") (pin "2") (pinfunction "A_2") (pintype "passive"))
      (node (ref "D6") (pin "2") (pinfunction "A_2") (pintype "passive"))
      (node (ref "D8") (pin "1") (pinfunction "1_1") (pintype "passive"))
      (node (ref "J3") (pin "2") (pinfunction "2_2") (pintype "passive"))
      (node (ref "J4") (pin "1") (pinfunction "1_1") (pintype "passive"))
      (node (ref "KEY1") (pin "2") (pinfunction "2_2") (pintype "passive"))
      (node (ref "KEY2") (pin "2") (pinfunction "2_2") (pintype "passive"))
      (node (ref "LED24") (pin "2") (pinfunction "2_2") (pintype "passive"))
      (node (ref "P2") (pin "2") (pinfunction "GND_2") (pintype "passive"))
      (node (ref "Q1") (pin "2") (pinfunction "E_2") (pintype "passive"))
      (node (ref "Q2") (pin "2") (pinfunction "E_2") (pintype "passive"))
      (node (ref "Q4") (pin "2") (pinfunction "S_2") (pintype "passive"))
      (node (ref "R15") (pin "2") (pinfunction "2_2") (pintype "passive"))
      (node (ref "R19") (pin "1") (pinfunction "1_1") (pintype "passive"))
      (node (ref "R21") (pin "1") (pinfunction "1_1") (pintype "passive"))
      (node (ref "R5") (pin "1") (pinfunction "1_1") (pintype "passive"))
      (node (ref "R6") (pin "1") (pinfunction "1_1") (pintype "passive"))
      (node (ref "R7") (pin "1") (pinfunction "1_1") (pintype "passive"))
      (node (ref "R8") (pin "1") (pinfunction "1_1") (pintype "passive"))
      (node (ref "U1") (pin "7") (pinfunction "GND_7") (pintype "passive"))
      (node (ref "U1") (pin "9") (pinfunction "EP_9") (pintype "passive"))
      (node (ref "U10") (pin "1") (pinfunction "GND/ADJ_1") (pintype "passive"))
      (node (ref "U2") (pin "6") (pinfunction "GND_6") (pintype "passive"))
      (node (ref "U3") (pin "1") (pinfunction "GND_1") (pintype "passive"))
      (node (ref "U3") (pin "15") (pinfunction "GND_15") (pintype "passive"))
      (node (ref "U3") (pin "38") (pinfunction "GND_38") (pintype "passive"))
      (node (ref "U3") (pin "39") (pinfunction "EP_39") (pintype "passive"))
      (node (ref "U5") (pin "1") (pinfunction "GND_1") (pintype "passive"))
      (node (ref "U5") (pin "10") (pinfunction "GND_10") (pintype "passive"))
      (node (ref "U5") (pin "11") (pinfunction "GND_11") (pintype "passive"))
      (node (ref "U5") (pin "19") (pinfunction "SENSE2_19") (pintype "passive"))
      (node (ref "U5") (pin "2") (pinfunction "SENSE1_2") (pintype "passive"))
      (node (ref "U5") (pin "20") (pinfunction "GND_20") (pintype "passive"))
      (node (ref "U5") (pin "21") (pinfunction "EP_21") (pintype "passive"))
      (node (ref "U6") (pin "1") (pinfunction "GND_1") (pintype "passive"))
      (node (ref "U6") (pin "7") (pinfunction "DIR_7") (pintype "passive"))
      (node (ref "U9") (pin "2") (pinfunction "BATN_2") (pintype "passive"))
      (node (ref "USB2") (pin "0") (pinfunction "0_0") (pintype "passive"))
      (node (ref "USB2") (pin "1") (pinfunction "B12_1") (pintype "passive"))
      (node (ref "USB2") (pin "6") (pinfunction "A12_6") (pintype "passive"))
    )
    (net (code "30") (name "Net-(C9-Pad1)") (class "Default")
      (node (ref "C9") (pin "1") (pinfunction "1_1") (pintype "passive"))
      (node (ref "R6") (pin "2") (pinfunction "2_2") (pintype "passive"))
    )
    (net (code "31") (name "Net-(D2-A)") (class "Default")
      (node (ref "D2") (pin "2") (pinfunction "A_2") (pintype "passive"))
      (node (ref "L2") (pin "2") (pinfunction "2_2") (pintype "passive"))
      (node (ref "Q4") (pin "3") (pinfunction "D_3") (pintype "passive"))
    )
    (net (code "32") (name "Net-(D3-A)") (class "Default")
      (node (ref "D3") (pin "1") (pinfunction "A_1") (pintype "passive"))
      (node (ref "R16") (pin "1") (pinfunction "1_1") (pintype "passive"))
    )
    (net (code "33") (name "Net-(D3-K)") (class "Default")
      (node (ref "D3") (pin "2") (pinfunction "K_2") (pintype "passive"))
      (node (ref "Q1") (pin "3") (pinfunction "C_3") (pintype "passive"))
    )
    (net (code "34") (name "Net-(D4-K)") (class "Default")
      (node (ref "C2") (pin "2") (pinfunction "2_2") (pintype "passive"))
      (node (ref "D4") (pin "1") (pinfunction "K_1") (pintype "passive"))
      (node (ref "L1") (pin "1") (pinfunction "1_1") (pintype "passive"))
      (node (ref "U1") (pin "8") (pinfunction "PH_8") (pintype "passive"))
    )
    (net (code "35") (name "Net-(D5-AK)") (class "Default")
      (node (ref "C17") (pin "2") (pinfunction "2_2") (pintype "passive"))
      (node (ref "D5") (pin "3") (pinfunction "AK_3") (pintype "passive"))
    )
    (net (code "36") (name "Net-(D5-K)") (class "Default")
      (node (ref "C16") (pin "1") (pinfunction "1_1") (pintype "passive"))
      (node (ref "D5") (pin "2") (pinfunction "K_2") (pintype "passive"))
      (node (ref "U5") (pin "18") (pinfunction "Vboot_18") (pintype "passive"))
    )
    (net (code "37") (name "Net-(D7-A)") (class "Default")
      (node (ref "D7") (pin "2") (pinfunction "A_2") (pintype "passive"))
      (node (ref "Q4") (pin "1") (pinfunction "G_1") (pintype "passive"))
      (node (ref "R26") (pin "1") (pinfunction "1_1") (pintype "passive"))
    )
    (net (code "38") (name "Net-(D7-C)") (class "Default")
      (node (ref "D7") (pin "1") (pinfunction "C_1") (pintype "passive"))
      (node (ref "R25") (pin "1") (pinfunction "1_1") (pintype "passive"))
      (node (ref "R26") (pin "2") (pinfunction "2_2") (pintype "passive"))
      (node (ref "U2") (pin "5") (pinfunction "DRV_5") (pintype "passive"))
    )
    (net (code "39") (name "Net-(J4-Pad2)") (class "Default")
      (node (ref "J4") (pin "2") (pinfunction "2_2") (pintype "passive"))
      (node (ref "R22") (pin "2") (pinfunction "2_2") (pintype "passive"))
    )
    (net (code "40") (name "Net-(J4-Pad3)") (class "Default")
      (node (ref "J4") (pin "3") (pinfunction "3_3") (pintype "passive"))
      (node (ref "R23") (pin "2") (pinfunction "2_2") (pintype "passive"))
    )
    (net (code "41") (name "Net-(LED2-A)") (class "Default")
      (node (ref "LED2") (pin "1") (pinfunction "A_1") (pintype "passive"))
      (node (ref "R13") (pin "1") (pinfunction "1_1") (pintype "passive"))
    )
    (net (code "42") (name "Net-(LED3-Pad2)") (class "Default")
      (node (ref "LED3") (pin "2") (pinfunction "2_2") (pintype "passive"))
      (node (ref "R20") (pin "2") (pinfunction "2_2") (pintype "passive"))
    )
    (net (code "43") (name "Net-(LED4-Pad2)") (class "Default")
      (node (ref "LED4") (pin "2") (pinfunction "2_2") (pintype "passive"))
      (node (ref "R21") (pin "2") (pinfunction "2_2") (pintype "passive"))
    )
    (net (code "44") (name "Net-(LED22-A)") (class "Default")
      (node (ref "LED22") (pin "1") (pinfunction "A_1") (pintype "passive"))
      (node (ref "R18") (pin "1") (pinfunction "1_1") (pintype "passive"))
    )
    (net (code "45") (name "Net-(LED22-K)") (class "Default")
      (node (ref "C52") (pin "2") (pinfunction "2_2") (pintype "passive"))
      (node (ref "L9") (pin "1") (pinfunction "1_1") (pintype "passive"))
      (node (ref "LED22") (pin "2") (pinfunction "K_2") (pintype "passive"))
      (node (ref "U9") (pin "4") (pinfunction "SW_4") (pintype "passive"))
    )
    (net (code "46") (name "Net-(LED23-A)") (class "Default")
      (node (ref "LED23") (pin "1") (pinfunction "A_1") (pintype "passive"))
      (node (ref "R17") (pin "1") (pinfunction "1_1") (pintype "passive"))
    )
    (net (code "47") (name "Net-(LED23-K)") (class "Default")
      (node (ref "C54") (pin "2") (pinfunction "2_2") (pintype "passive"))
      (node (ref "L8") (pin "1") (pinfunction "1_1") (pintype "passive"))
      (node (ref "LED23") (pin "2") (pinfunction "K_2") (pintype "passive"))
      (node (ref "U8") (pin "4") (pinfunction "SW_4") (pintype "passive"))
    )
    (net (code "48") (name "Net-(LED24-Pad1)") (class "Default")
      (node (ref "LED24") (pin "1") (pinfunction "1_1") (pintype "passive"))
      (node (ref "R29") (pin "1") (pinfunction "1_1") (pintype "passive"))
    )
    (net (code "49") (name "Net-(Q1-B)") (class "Default")
      (node (ref "C45") (pin "2") (pinfunction "2_2") (pintype "passive"))
      (node (ref "Q1") (pin "1") (pinfunction "B_1") (pintype "passive"))
      (node (ref "Q2") (pin "3") (pinfunction "C_3") (pintype "passive"))
      (node (ref "R24") (pin "1") (pinfunction "1_1") (pintype "passive"))
    )
    (net (code "50") (name "Net-(Q2-B)") (class "Default")
      (node (ref "Q2") (pin "1") (pinfunction "B_1") (pintype "passive"))
      (node (ref "R25") (pin "2") (pinfunction "2_2") (pintype "passive"))
    )
    (net (code "51") (name "Net-(U1-BOOT)") (class "Default")
      (node (ref "C2") (pin "1") (pinfunction "1_1") (pintype "passive"))
      (node (ref "U1") (pin "1") (pinfunction "BOOT_1") (pintype "passive"))
    )
    (net (code "52") (name "Net-(U1-COMP)") (class "Default")
      (node (ref "C10") (pin "2") (pinfunction "2_2") (pintype "passive"))
      (node (ref "C9") (pin "2") (pinfunction "2_2") (pintype "passive"))
      (node (ref "U1") (pin "6") (pinfunction "COMP_6") (pintype "passive"))
    )
    (net (code "53") (name "Net-(U1-EN)") (class "Default")
      (node (ref "R4") (pin "1") (pinfunction "1_1") (pintype "passive"))
      (node (ref "R8") (pin "2") (pinfunction "2_2") (pintype "passive"))
      (node (ref "U1") (pin "3") (pinfunction "EN_3") (pintype "passive"))
    )
    (net (code "54") (name "Net-(U1-SS)") (class "Default")
      (node (ref "C11") (pin "2") (pinfunction "2_2") (pintype "passive"))
      (node (ref "U1") (pin "4") (pinfunction "SS_4") (pintype "passive"))
    )
    (net (code "55") (name "Net-(U1-VSENSE)") (class "Default")
      (node (ref "R3") (pin "1") (pinfunction "1_1") (pintype "passive"))
      (node (ref "R7") (pin "2") (pinfunction "2_2") (pintype "passive"))
      (node (ref "U1") (pin "5") (pinfunction "VSENSE_5") (pintype "passive"))
    )
    (net (code "56") (name "Net-(U2-CSN)") (class "Default")
      (node (ref "L2") (pin "1") (pinfunction "1_1") (pintype "passive"))
      (node (ref "R14") (pin "2") (pinfunction "2_2") (pintype "passive"))
      (node (ref "U2") (pin "1") (pinfunction "CSN_1") (pintype "passive"))
    )
    (net (code "57") (name "Net-(U2-FB)") (class "Default")
      (node (ref "C48") (pin "2") (pinfunction "2_2") (pintype "passive"))
      (node (ref "R12") (pin "1") (pinfunction "1_1") (pintype "passive"))
      (node (ref "R15") (pin "1") (pinfunction "1_1") (pintype "passive"))
      (node (ref "U2") (pin "2") (pinfunction "FB_2") (pintype "passive"))
    )
    (net (code "58") (name "Net-(U2-VCC)") (class "Default")
      (node (ref "C46") (pin "2") (pinfunction "2_2") (pintype "passive"))
      (node (ref "U2") (pin "4") (pinfunction "VCC_4") (pintype "passive"))
    )
    (net (code "59") (name "Net-(U3-IO2)") (class "Default")
      (node (ref "R2") (pin "2") (pinfunction "2_2") (pintype "passive"))
      (node (ref "U3") (pin "24") (pinfunction "IO2_24") (pintype "passive"))
    )
    (net (code "60") (name "Net-(U3-IO13)") (class "Default")
      (node (ref "R28") (pin "2") (pinfunction "2_2") (pintype "passive"))
      (node (ref "U3") (pin "16") (pinfunction "IO13_16") (pintype "passive"))
    )
    (net (code "61") (name "Net-(U3-IO15)") (class "Default")
      (node (ref "R1") (pin "2") (pinfunction "2_2") (pintype "passive"))
      (node (ref "U3") (pin "23") (pinfunction "IO15_23") (pintype "passive"))
    )
    (net (code "62") (name "Net-(U5-Vcp)") (class "Default")
      (node (ref "C17") (pin "1") (pinfunction "1_1") (pintype "passive"))
      (node (ref "U5") (pin "17") (pinfunction "Vcp_17") (pintype "passive"))
    )
    (net (code "63") (name "Net-(U5-Vref)") (class "Default")
      (node (ref "C19") (pin "1") (pinfunction "1_1") (pintype "passive"))
      (node (ref "U5") (pin "16") (pinfunction "Vref_16") (pintype "passive"))
    )
    (net (code "64") (name "Net-(U8-BLAS)") (class "Default")
      (node (ref "C54") (pin "1") (pinfunction "1_1") (pintype "passive"))
      (node (ref "R17") (pin "2") (pinfunction "2_2") (pintype "passive"))
      (node (ref "U8") (pin "3") (pinfunction "BLAS_3") (pintype "passive"))
    )
    (net (code "65") (name "Net-(U8-ISET)") (class "Default")
      (node (ref "C53") (pin "1") (pinfunction "1_1") (pintype "passive"))
      (node (ref "R27") (pin "2") (pinfunction "2_2") (pintype "passive"))
      (node (ref "U8") (pin "1") (pinfunction "ISET_1") (pintype "passive"))
    )
    (net (code "66") (name "Net-(U9-BLAS)") (class "Default")
      (node (ref "C52") (pin "1") (pinfunction "1_1") (pintype "passive"))
      (node (ref "R18") (pin "2") (pinfunction "2_2") (pintype "passive"))
      (node (ref "U9") (pin "3") (pinfunction "BLAS_3") (pintype "passive"))
    )
    (net (code "67") (name "Net-(U9-ISET)") (class "Default")
      (node (ref "C43") (pin "1") (pinfunction "1_1") (pintype "passive"))
      (node (ref "R19") (pin "2") (pinfunction "2_2") (pintype "passive"))
      (node (ref "U9") (pin "1") (pinfunction "ISET_1") (pintype "passive"))
    )
    (net (code "68") (name "unconnected-(CN2-Pad4)") (class "Default")
      (node (ref "CN2") (pin "4") (pinfunction "4_4") (pintype "passive+no_connect"))
    )
    (net (code "69") (name "unconnected-(CN2-Pad5)") (class "Default")
      (node (ref "CN2") (pin "5") (pinfunction "5_5") (pintype "passive+no_connect"))
    )
    (net (code "70") (name "unconnected-(P2-AD0-Pad7)") (class "Default")
      (node (ref "P2") (pin "7") (pinfunction "AD0_7") (pintype "passive+no_connect"))
    )
    (net (code "71") (name "unconnected-(P2-INT-Pad8)") (class "Default")
      (node (ref "P2") (pin "8") (pinfunction "INT_8") (pintype "passive+no_connect"))
    )
    (net (code "72") (name "unconnected-(P2-XCL-Pad6)") (class "Default")
      (node (ref "P2") (pin "6") (pinfunction "XCL_6") (pintype "passive+no_connect"))
    )
    (net (code "73") (name "unconnected-(P2-XDA-Pad5)") (class "Default")
      (node (ref "P2") (pin "5") (pinfunction "XDA_5") (pintype "passive+no_connect"))
    )
    (net (code "74") (name "unconnected-(SW2-Pad1)") (class "Default")
      (node (ref "SW2") (pin "1") (pinfunction "1_1") (pintype "passive+no_connect"))
    )
    (net (code "75") (name "unconnected-(SW2-Pad4)") (class "Default")
      (node (ref "SW2") (pin "4") (pinfunction "4_4") (pintype "passive+no_connect"))
    )
    (net (code "76") (name "unconnected-(SW2-Pad5)") (class "Default")
      (node (ref "SW2") (pin "5") (pinfunction "5_5") (pintype "passive+no_connect"))
    )
    (net (code "77") (name "unconnected-(U3-CLK-Pad20)") (class "Default")
      (node (ref "U3") (pin "20") (pinfunction "CLK_20") (pintype "passive+no_connect"))
    )
    (net (code "78") (name "unconnected-(U3-CMD-Pad19)") (class "Default")
      (node (ref "U3") (pin "19") (pinfunction "CMD_19") (pintype "passive+no_connect"))
    )
    (net (code "79") (name "unconnected-(U3-IO12-Pad14)") (class "Default")
      (node (ref "U3") (pin "14") (pinfunction "IO12_14") (pintype "passive+no_connect"))
    )
    (net (code "80") (name "unconnected-(U3-IO14-Pad13)") (class "Default")
      (node (ref "U3") (pin "13") (pinfunction "IO14_13") (pintype "passive+no_connect"))
    )
    (net (code "81") (name "unconnected-(U3-IO17-Pad28)") (class "Default")
      (node (ref "U3") (pin "28") (pinfunction "IO17_28") (pintype "passive+no_connect"))
    )
    (net (code "82") (name "unconnected-(U3-IO21-Pad33)") (class "Default")
      (node (ref "U3") (pin "33") (pinfunction "IO21_33") (pintype "passive+no_connect"))
    )
    (net (code "83") (name "unconnected-(U3-IO26-Pad11)") (class "Default")
      (node (ref "U3") (pin "11") (pinfunction "IO26_11") (pintype "passive+no_connect"))
    )
    (net (code "84") (name "unconnected-(U3-IO27-Pad12)") (class "Default")
      (node (ref "U3") (pin "12") (pinfunction "IO27_12") (pintype "passive+no_connect"))
    )
    (net (code "85") (name "unconnected-(U3-IO35-Pad7)") (class "Default")
      (node (ref "U3") (pin "7") (pinfunction "IO35_7") (pintype "passive+no_connect"))
    )
    (net (code "86") (name "unconnected-(U3-NC-Pad32)") (class "Default")
      (node (ref "U3") (pin "32") (pinfunction "NC_32") (pintype "passive+no_connect"))
    )
    (net (code "87") (name "unconnected-(U3-SD0-Pad21)") (class "Default")
      (node (ref "U3") (pin "21") (pinfunction "SD0_21") (pintype "passive+no_connect"))
    )
    (net (code "88") (name "unconnected-(U3-SD1-Pad22)") (class "Default")
      (node (ref "U3") (pin "22") (pinfunction "SD1_22") (pintype "passive+no_connect"))
    )
    (net (code "89") (name "unconnected-(U3-SD2-Pad17)") (class "Default")
      (node (ref "U3") (pin "17") (pinfunction "SD2_17") (pintype "passive+no_connect"))
    )
    (net (code "90") (name "unconnected-(U3-SD3-Pad18)") (class "Default")
      (node (ref "U3") (pin "18") (pinfunction "SD3_18") (pintype "passive+no_connect"))
    )
    (net (code "91") (name "unconnected-(U3-SENSOR_VN-Pad5)") (class "Default")
      (node (ref "U3") (pin "5") (pinfunction "SENSOR_VN_5") (pintype "passive+no_connect"))
    )
    (net (code "92") (name "unconnected-(U3-SENSOR_VP-Pad4)") (class "Default")
      (node (ref "U3") (pin "4") (pinfunction "SENSOR_VP_4") (pintype "passive+no_connect"))
    )
    (net (code "93") (name "unconnected-(U6-GPO-Pad4)") (class "Default")
      (node (ref "U6") (pin "4") (pinfunction "GPO_4") (pintype "passive+no_connect"))
    )
    (net (code "94") (name "unconnected-(U6-OUT-Pad2)") (class "Default")
      (node (ref "U6") (pin "2") (pinfunction "OUT_2") (pintype "passive+no_connect"))
    )
    (net (code "95") (name "unconnected-(USB2-A5-Pad3)") (class "Default")
      (node (ref "USB2") (pin "3") (pinfunction "A5_3") (pintype "passive+no_connect"))
    )
    (net (code "96") (name "unconnected-(USB2-B5-Pad4)") (class "Default")
      (node (ref "USB2") (pin "4") (pinfunction "B5_4") (pintype "passive+no_connect"))
    )
  )
)
